# cubesatsim-main-1_0.net
KiCad netlist of a schematic drawn in EAGLE
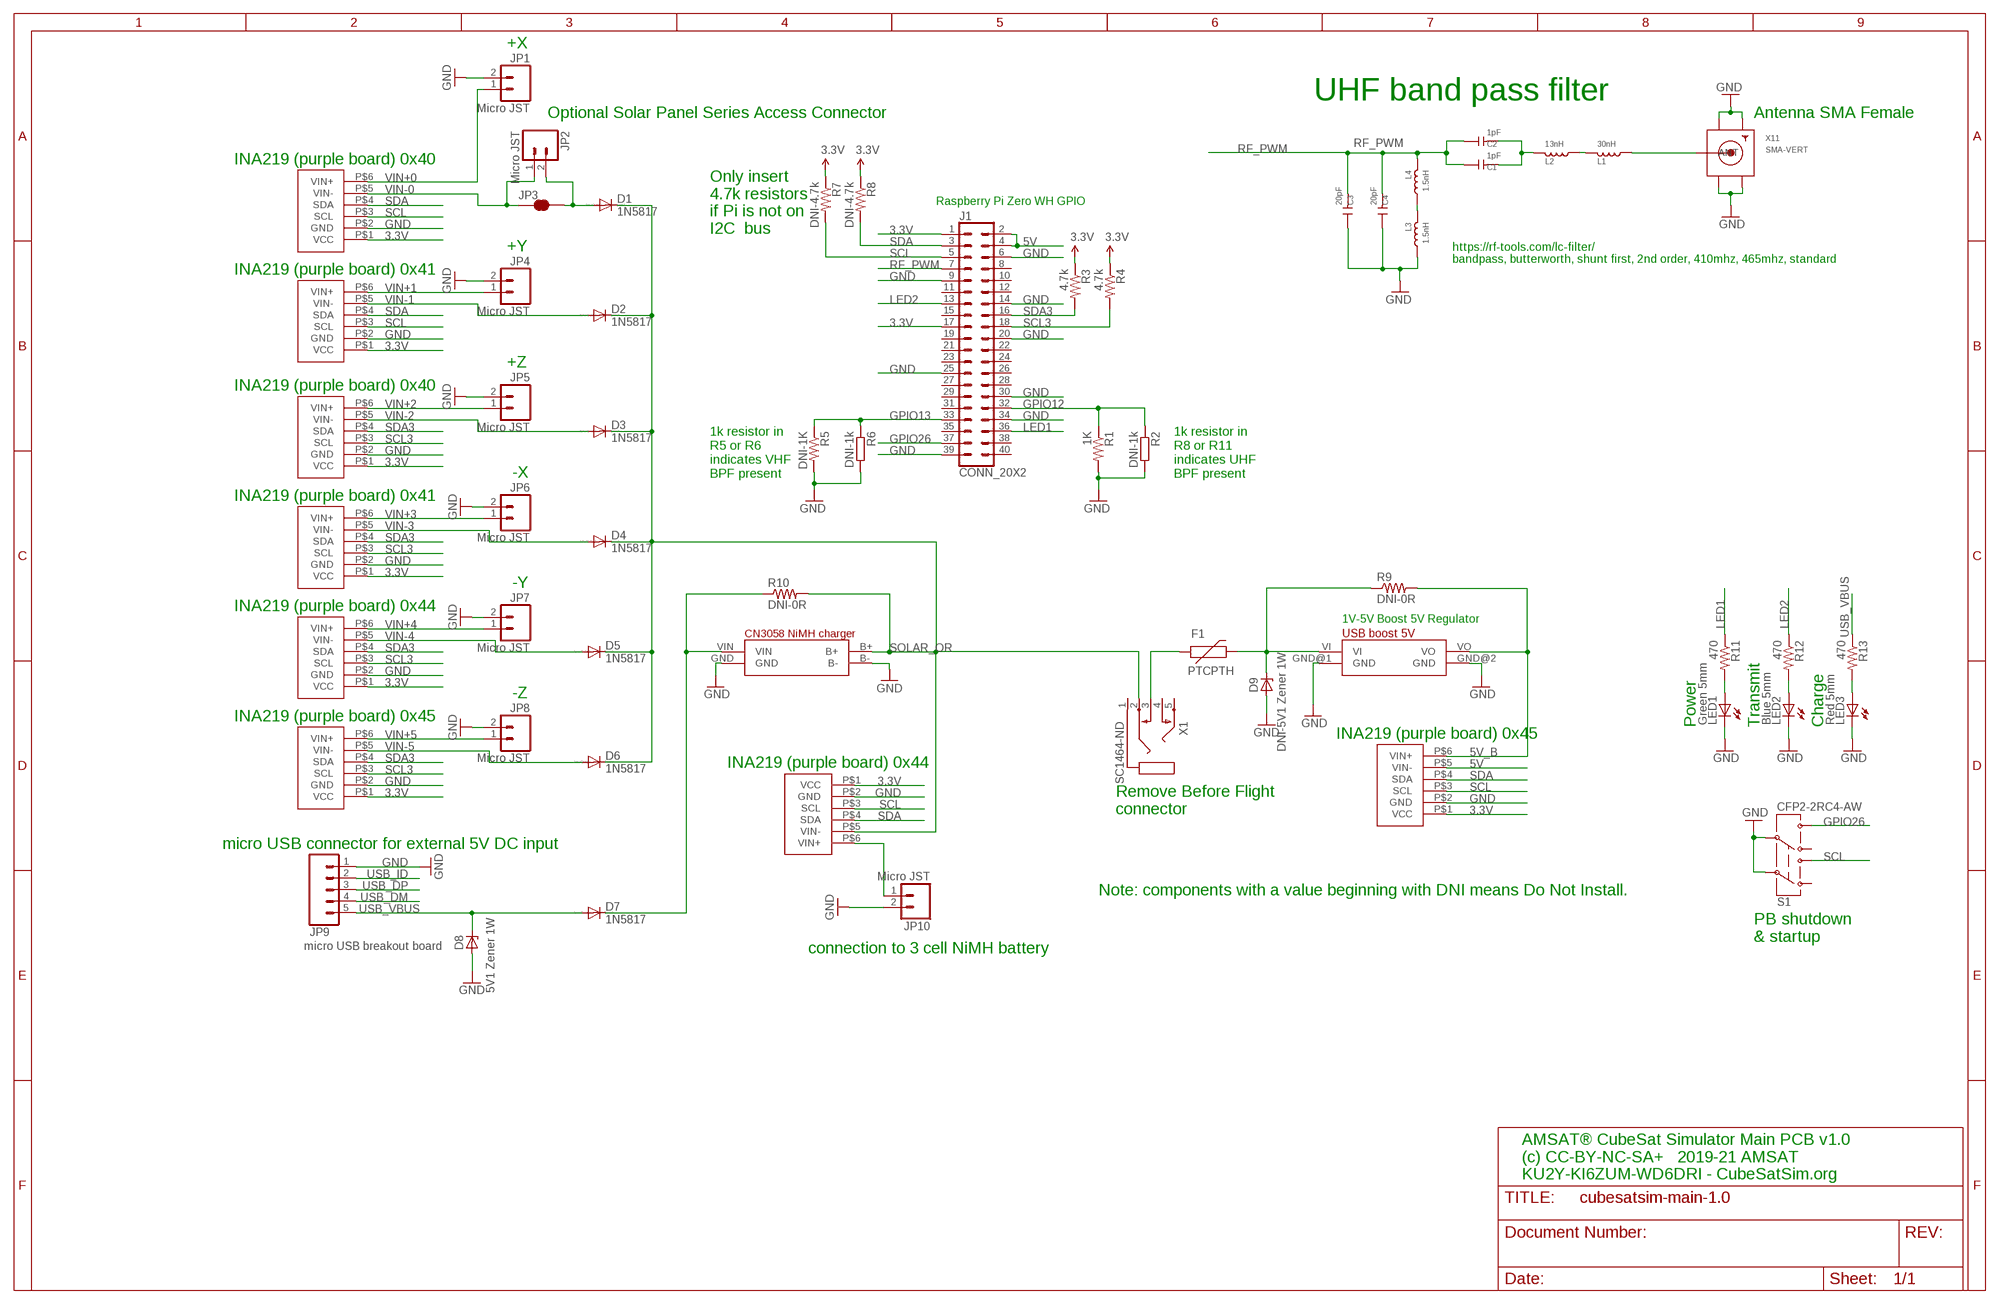
[diagram p0: schematic, sheet 1]

(export (version "E")
  (design (tool "Eeschema 10.0.6"))
  (components
    (comp (ref "C1")
      (value "1pF")
      (footprint "eagle-import:C0603")
      (libsource (lib "eagle-import") (part "CERAMIC-10PF-50V-5%-NPO(0603)"))
    )
    (comp (ref "C2")
      (value "1pF")
      (footprint "eagle-import:C0603")
      (libsource (lib "eagle-import") (part "CERAMIC-10PF-50V-5%-NPO(0603)"))
    )
    (comp (ref "C3")
      (value "20pF")
      (footprint "eagle-import:C0603")
      (libsource (lib "eagle-import") (part "CERAMIC-10PF-50V-5%-NPO(0603)"))
    )
    (comp (ref "C4")
      (value "20pF")
      (footprint "eagle-import:C0603")
      (libsource (lib "eagle-import") (part "CERAMIC-10PF-50V-5%-NPO(0603)"))
    )
    (comp (ref "D1")
      (value "1N5817")
      (footprint "eagle-import:D-2.5")
      (libsource (lib "eagle-import") (part "DIODE-D-2.5"))
    )
    (comp (ref "D2")
      (value "1N5817")
      (footprint "eagle-import:D-2.5")
      (libsource (lib "eagle-import") (part "DIODE-D-2.5"))
    )
    (comp (ref "D3")
      (value "1N5817")
      (footprint "eagle-import:D-2.5")
      (libsource (lib "eagle-import") (part "DIODE-D-2.5"))
    )
    (comp (ref "D4")
      (value "1N5817")
      (footprint "eagle-import:D-2.5")
      (libsource (lib "eagle-import") (part "DIODE-D-2.5"))
    )
    (comp (ref "D5")
      (value "1N5817")
      (footprint "eagle-import:D-2.5")
      (libsource (lib "eagle-import") (part "DIODE-D-2.5"))
    )
    (comp (ref "D6")
      (value "1N5817")
      (footprint "eagle-import:D-2.5")
      (libsource (lib "eagle-import") (part "DIODE-D-2.5"))
    )
    (comp (ref "D7")
      (value "1N5817")
      (footprint "eagle-import:D-2.5")
      (libsource (lib "eagle-import") (part "DIODE-D-2.5"))
    )
    (comp (ref "D8")
      (value "5V1 Zener 1W")
      (footprint "eagle-import:ZDIO-2.5")
      (libsource (lib "eagle-import") (part "ZENER-DIODEZD-2.5"))
    )
    (comp (ref "D9")
      (value "DNI-5V1 Zener 1W")
      (footprint "eagle-import:ZDIO-2.5")
      (libsource (lib "eagle-import") (part "ZENER-DIODEZD-2.5"))
    )
    (comp (ref "F1")
      (value "PTCPTH")
      (footprint "eagle-import:PTC")
      (libsource (lib "eagle-import") (part "PTCPTH"))
    )
    (comp (ref "J1")
      (value "CONN_20X2")
      (footprint "eagle-import:2X20")
      (libsource (lib "eagle-import") (part "CONN_20X2"))
    )
    (comp (ref "JP1")
      (value "Micro JST")
      (footprint "eagle-import:JST-2-PTH-VERT")
      (libsource (lib "eagle-import") (part "M02JST-PTH-VERT"))
    )
    (comp (ref "JP2")
      (value "Micro JST")
      (footprint "eagle-import:JST-2-PTH-VERT")
      (libsource (lib "eagle-import") (part "M02JST-PTH-VERT"))
    )
    (comp (ref "JP3")
      (value "VDD-EN")
      (footprint "eagle-import:SMT-JUMPER_2_NC_TRACE_SILK")
      (libsource (lib "eagle-import") (part "JUMPER-SMT_2_NC_TRACE_SILK"))
    )
    (comp (ref "JP4")
      (value "Micro JST")
      (footprint "eagle-import:JST-2-PTH-VERT")
      (libsource (lib "eagle-import") (part "M02JST-PTH-VERT"))
    )
    (comp (ref "JP5")
      (value "Micro JST")
      (footprint "eagle-import:JST-2-PTH-VERT")
      (libsource (lib "eagle-import") (part "M02JST-PTH-VERT"))
    )
    (comp (ref "JP6")
      (value "Micro JST")
      (footprint "eagle-import:JST-2-PTH-VERT")
      (libsource (lib "eagle-import") (part "M02JST-PTH-VERT"))
    )
    (comp (ref "JP7")
      (value "Micro JST")
      (footprint "eagle-import:JST-2-PTH-VERT")
      (libsource (lib "eagle-import") (part "M02JST-PTH-VERT"))
    )
    (comp (ref "JP8")
      (value "Micro JST")
      (footprint "eagle-import:JST-2-PTH-VERT")
      (libsource (lib "eagle-import") (part "M02JST-PTH-VERT"))
    )
    (comp (ref "JP9")
      (value "micro USB breakout board")
      (footprint "eagle-import:1X05_NO_SILK")
      (libsource (lib "eagle-import") (part "M05NO_SILK"))
    )
    (comp (ref "JP10")
      (value "Micro JST")
      (footprint "eagle-import:JST-2-PTH-VERT")
      (libsource (lib "eagle-import") (part "M02JST-PTH-VERT"))
    )
    (comp (ref "L1")
      (value "30nH")
      (footprint "eagle-import:L0603")
      (fields (field (name "MPN") "BLM18AG121SN1D"))
      (libsource (lib "eagle-import") (part "SMD-FERRITE-CHIP-120-OHM-500MA(0603)"))
    )
    (comp (ref "L2")
      (value "13nH")
      (footprint "eagle-import:L0603")
      (fields (field (name "MPN") "BLM18AG121SN1D"))
      (libsource (lib "eagle-import") (part "SMD-FERRITE-CHIP-120-OHM-500MA(0603)"))
    )
    (comp (ref "L3")
      (value "1.5nH")
      (footprint "eagle-import:L0603")
      (fields (field (name "MPN") "BLM18AG121SN1D"))
      (libsource (lib "eagle-import") (part "SMD-FERRITE-CHIP-120-OHM-500MA(0603)"))
    )
    (comp (ref "L4")
      (value "1.5nH")
      (footprint "eagle-import:L0603")
      (fields (field (name "MPN") "BLM18AG121SN1D"))
      (libsource (lib "eagle-import") (part "SMD-FERRITE-CHIP-120-OHM-500MA(0603)"))
    )
    (comp (ref "LED1")
      (value "Green 5mm")
      (footprint "eagle-import:LED3MM")
      (libsource (lib "eagle-import") (part "LED3MM"))
    )
    (comp (ref "LED2")
      (value "Blue 5mm")
      (footprint "eagle-import:LED3MM")
      (libsource (lib "eagle-import") (part "LED3MM"))
    )
    (comp (ref "LED3")
      (value "Red 5mm")
      (footprint "eagle-import:LED3MM")
      (libsource (lib "eagle-import") (part "LED3MM"))
    )
    (comp (ref "R1")
      (value "1K")
      (footprint "eagle-import:AXIAL-0.1EZ")
      (libsource (lib "eagle-import") (part "RESISTORPTH-1/4W-VERT-KIT"))
    )
    (comp (ref "R2")
      (value "DNI-1k")
      (footprint "eagle-import:R0603")
      (libsource (lib "eagle-import") (part "R-EU_R0603"))
    )
    (comp (ref "R3")
      (value "4.7k")
      (footprint "eagle-import:AXIAL-0.1EZ")
      (libsource (lib "eagle-import") (part "RESISTORPTH-1/4W-VERT-KIT"))
    )
    (comp (ref "R4")
      (value "4.7k")
      (footprint "eagle-import:AXIAL-0.1EZ")
      (libsource (lib "eagle-import") (part "RESISTORPTH-1/4W-VERT-KIT"))
    )
    (comp (ref "R5")
      (value "DNI-1K")
      (footprint "eagle-import:AXIAL-0.1EZ")
      (libsource (lib "eagle-import") (part "RESISTORPTH-1/4W-VERT-KIT"))
    )
    (comp (ref "R6")
      (value "DNI-1k")
      (footprint "eagle-import:R0603")
      (libsource (lib "eagle-import") (part "R-EU_R0603"))
    )
    (comp (ref "R7")
      (value "DNI-4.7k")
      (footprint "eagle-import:AXIAL-0.1EZ")
      (libsource (lib "eagle-import") (part "RESISTORPTH-1/4W-VERT-KIT"))
    )
    (comp (ref "R8")
      (value "DNI-4.7k")
      (footprint "eagle-import:AXIAL-0.1EZ")
      (libsource (lib "eagle-import") (part "RESISTORPTH-1/4W-VERT-KIT"))
    )
    (comp (ref "R9")
      (value "DNI-0R")
      (footprint "eagle-import:AXIAL-0.1EZ")
      (libsource (lib "eagle-import") (part "RESISTORPTH-1/4W-VERT-KIT"))
    )
    (comp (ref "R10")
      (value "DNI-0R")
      (footprint "eagle-import:AXIAL-0.1EZ")
      (libsource (lib "eagle-import") (part "RESISTORPTH-1/4W-VERT-KIT"))
    )
    (comp (ref "R11")
      (value "470")
      (footprint "eagle-import:AXIAL-0.1EZ")
      (libsource (lib "eagle-import") (part "RESISTORPTH-1/4W-VERT-KIT"))
    )
    (comp (ref "R12")
      (value "470")
      (footprint "eagle-import:AXIAL-0.1EZ")
      (libsource (lib "eagle-import") (part "RESISTORPTH-1/4W-VERT-KIT"))
    )
    (comp (ref "R13")
      (value "470")
      (footprint "eagle-import:AXIAL-0.1EZ")
      (libsource (lib "eagle-import") (part "RESISTORPTH-1/4W-VERT-KIT"))
    )
    (comp (ref "S1")
      (value "CFP2-2RC4-AW")
      (footprint "eagle-import:OS")
      (libsource (lib "eagle-import") (part "SWITCH-DPDTOS"))
    )
    (comp (ref "U1")
      (value "INA219 purple board")
      (footprint "eagle-import:INA219")
      (libsource (lib "eagle-import") (part "INA219"))
    )
    (comp (ref "U2")
      (value "INA219 purple board")
      (footprint "eagle-import:INA219")
      (libsource (lib "eagle-import") (part "INA219"))
    )
    (comp (ref "U3")
      (value "INA219 purple board")
      (footprint "eagle-import:INA219")
      (libsource (lib "eagle-import") (part "INA219"))
    )
    (comp (ref "U4")
      (value "INA219 purple board")
      (footprint "eagle-import:INA219")
      (libsource (lib "eagle-import") (part "INA219"))
    )
    (comp (ref "U5")
      (value "INA219 purple board")
      (footprint "eagle-import:INA219")
      (libsource (lib "eagle-import") (part "INA219"))
    )
    (comp (ref "U6")
      (value "CN3085-MODULE")
      (footprint "eagle-import:CN3085-MODULE")
      (libsource (lib "eagle-import") (part "CN3085-MODULE"))
    )
    (comp (ref "U7")
      (value "1V-5V Boost 5V Regulator")
      (footprint "eagle-import:USB-BOOST")
      (libsource (lib "eagle-import") (part "USB-BOOST"))
    )
    (comp (ref "U8")
      (value "INA219 purple board")
      (footprint "eagle-import:INA219")
      (libsource (lib "eagle-import") (part "INA219"))
    )
    (comp (ref "U9")
      (value "INA219 purple board")
      (footprint "eagle-import:INA219")
      (libsource (lib "eagle-import") (part "INA219"))
    )
    (comp (ref "U10")
      (value "INA219 purple board")
      (footprint "eagle-import:INA219")
      (libsource (lib "eagle-import") (part "INA219"))
    )
    (comp (ref "X1")
      (value "SC1464-ND")
      (footprint "eagle-import:PG203J")
      (libsource (lib "eagle-import") (part "PG203J"))
    )
    (comp (ref "X11")
      (value "SMA-VERT")
      (footprint "eagle-import:SMA-VERT")
      (libsource (lib "eagle-import") (part "SMA-VERT"))
    )
  )
  (nets
    (net (code "1") (name "/5V") (class "Default")
      (node (ref "J1") (pin "2") (pinfunction "2_2") (pintype "passive"))
      (node (ref "J1") (pin "4") (pinfunction "4_4") (pintype "passive"))
      (node (ref "U9") (pin "P$5") (pinfunction "VIN-_P$5") (pintype "bidirectional"))
    )
    (net (code "2") (name "/5V_B") (class "Default")
      (node (ref "R9") (pin "P$2") (pinfunction "2_P$2") (pintype "passive"))
      (node (ref "U7") (pin "VO") (pinfunction "VO_VO") (pintype "bidirectional"))
      (node (ref "U9") (pin "P$6") (pinfunction "VIN+_P$6") (pintype "bidirectional"))
    )
    (net (code "3") (name "/GPIO12") (class "Default")
      (node (ref "J1") (pin "32") (pinfunction "32_32") (pintype "passive"))
      (node (ref "R1") (pin "P$1") (pinfunction "1_P$1") (pintype "passive"))
      (node (ref "R2") (pin "1") (pinfunction "1_1") (pintype "passive"))
    )
    (net (code "4") (name "/GPIO13") (class "Default")
      (node (ref "J1") (pin "33") (pinfunction "33_33") (pintype "passive"))
      (node (ref "R5") (pin "P$1") (pinfunction "1_P$1") (pintype "passive"))
      (node (ref "R6") (pin "1") (pinfunction "1_1") (pintype "passive"))
    )
    (net (code "5") (name "/GPIO26") (class "Default")
      (node (ref "J1") (pin "37") (pinfunction "37_37") (pintype "passive"))
      (node (ref "S1") (pin "6") (pinfunction "6_6") (pintype "bidirectional"))
    )
    (net (code "6") (name "/LED1") (class "Default")
      (node (ref "J1") (pin "36") (pinfunction "36_36") (pintype "passive"))
      (node (ref "R11") (pin "P$1") (pinfunction "1_P$1") (pintype "passive"))
    )
    (net (code "7") (name "/LED2") (class "Default")
      (node (ref "J1") (pin "13") (pinfunction "13_13") (pintype "passive"))
      (node (ref "R12") (pin "P$1") (pinfunction "1_P$1") (pintype "passive"))
    )
    (net (code "8") (name "/RF_PWM") (class "Default")
      (node (ref "C1") (pin "1") (pinfunction "1_1") (pintype "passive"))
      (node (ref "C2") (pin "1") (pinfunction "1_1") (pintype "passive"))
      (node (ref "C3") (pin "2") (pinfunction "2_2") (pintype "passive"))
      (node (ref "C4") (pin "2") (pinfunction "2_2") (pintype "passive"))
      (node (ref "J1") (pin "7") (pinfunction "7_7") (pintype "passive"))
      (node (ref "L4") (pin "1") (pinfunction "1_1") (pintype "passive"))
    )
    (net (code "9") (name "/SCL") (class "Default")
      (node (ref "J1") (pin "5") (pinfunction "5_5") (pintype "passive"))
      (node (ref "R7") (pin "P$2") (pinfunction "2_P$2") (pintype "passive"))
      (node (ref "S1") (pin "3") (pinfunction "3_3") (pintype "bidirectional"))
      (node (ref "U1") (pin "P$3") (pinfunction "SCL_P$3") (pintype "bidirectional"))
      (node (ref "U10") (pin "P$3") (pinfunction "SCL_P$3") (pintype "bidirectional"))
      (node (ref "U2") (pin "P$3") (pinfunction "SCL_P$3") (pintype "bidirectional"))
      (node (ref "U9") (pin "P$3") (pinfunction "SCL_P$3") (pintype "bidirectional"))
    )
    (net (code "10") (name "/SCL3") (class "Default")
      (node (ref "J1") (pin "18") (pinfunction "18_18") (pintype "passive"))
      (node (ref "R4") (pin "P$2") (pinfunction "2_P$2") (pintype "passive"))
      (node (ref "U3") (pin "P$3") (pinfunction "SCL_P$3") (pintype "bidirectional"))
      (node (ref "U4") (pin "P$3") (pinfunction "SCL_P$3") (pintype "bidirectional"))
      (node (ref "U5") (pin "P$3") (pinfunction "SCL_P$3") (pintype "bidirectional"))
      (node (ref "U8") (pin "P$3") (pinfunction "SCL_P$3") (pintype "bidirectional"))
    )
    (net (code "11") (name "/SDA") (class "Default")
      (node (ref "J1") (pin "3") (pinfunction "3_3") (pintype "passive"))
      (node (ref "R8") (pin "P$2") (pinfunction "2_P$2") (pintype "passive"))
      (node (ref "U1") (pin "P$4") (pinfunction "SDA_P$4") (pintype "bidirectional"))
      (node (ref "U10") (pin "P$4") (pinfunction "SDA_P$4") (pintype "bidirectional"))
      (node (ref "U2") (pin "P$4") (pinfunction "SDA_P$4") (pintype "bidirectional"))
      (node (ref "U9") (pin "P$4") (pinfunction "SDA_P$4") (pintype "bidirectional"))
    )
    (net (code "12") (name "/SDA3") (class "Default")
      (node (ref "J1") (pin "16") (pinfunction "16_16") (pintype "passive"))
      (node (ref "R3") (pin "P$2") (pinfunction "2_P$2") (pintype "passive"))
      (node (ref "U3") (pin "P$4") (pinfunction "SDA_P$4") (pintype "bidirectional"))
      (node (ref "U4") (pin "P$4") (pinfunction "SDA_P$4") (pintype "bidirectional"))
      (node (ref "U5") (pin "P$4") (pinfunction "SDA_P$4") (pintype "bidirectional"))
      (node (ref "U8") (pin "P$4") (pinfunction "SDA_P$4") (pintype "bidirectional"))
    )
    (net (code "13") (name "/SOLAR_OR") (class "Default")
      (node (ref "D1") (pin "C") (pinfunction "C_C") (pintype "passive"))
      (node (ref "D2") (pin "C") (pinfunction "C_C") (pintype "passive"))
      (node (ref "D3") (pin "C") (pinfunction "C_C") (pintype "passive"))
      (node (ref "D4") (pin "C") (pinfunction "C_C") (pintype "passive"))
      (node (ref "D5") (pin "C") (pinfunction "C_C") (pintype "passive"))
      (node (ref "D6") (pin "C") (pinfunction "C_C") (pintype "passive"))
      (node (ref "R10") (pin "P$2") (pinfunction "2_P$2") (pintype "passive"))
      (node (ref "U10") (pin "P$5") (pinfunction "VIN-_P$5") (pintype "bidirectional"))
      (node (ref "U6") (pin "B+") (pinfunction "B+_B+") (pintype "bidirectional"))
      (node (ref "X1") (pin "2") (pinfunction "2_2") (pintype "passive"))
    )
    (net (code "14") (name "/USB_DM") (class "Default")
      (node (ref "JP9") (pin "4") (pinfunction "4_4") (pintype "passive"))
    )
    (net (code "15") (name "/USB_DP") (class "Default")
      (node (ref "JP9") (pin "3") (pinfunction "3_3") (pintype "passive"))
    )
    (net (code "16") (name "/USB_ID") (class "Default")
      (node (ref "JP9") (pin "2") (pinfunction "2_2") (pintype "passive"))
    )
    (net (code "17") (name "/USB_VBUS") (class "Default")
      (node (ref "D7") (pin "A") (pinfunction "A_A") (pintype "passive"))
      (node (ref "D8") (pin "C") (pinfunction "C_C") (pintype "passive"))
      (node (ref "JP9") (pin "5") (pinfunction "5_5") (pintype "passive"))
      (node (ref "R13") (pin "P$1") (pinfunction "1_P$1") (pintype "passive"))
    )
    (net (code "18") (name "/VIN+0") (class "Default")
      (node (ref "JP1") (pin "1") (pinfunction "1_1") (pintype "passive"))
      (node (ref "U1") (pin "P$6") (pinfunction "VIN+_P$6") (pintype "bidirectional"))
    )
    (net (code "19") (name "/VIN+1") (class "Default")
      (node (ref "JP4") (pin "1") (pinfunction "1_1") (pintype "passive"))
      (node (ref "U2") (pin "P$6") (pinfunction "VIN+_P$6") (pintype "bidirectional"))
    )
    (net (code "20") (name "/VIN+2") (class "Default")
      (node (ref "JP5") (pin "1") (pinfunction "1_1") (pintype "passive"))
      (node (ref "U3") (pin "P$6") (pinfunction "VIN+_P$6") (pintype "bidirectional"))
    )
    (net (code "21") (name "/VIN+3") (class "Default")
      (node (ref "JP6") (pin "1") (pinfunction "1_1") (pintype "passive"))
      (node (ref "U4") (pin "P$6") (pinfunction "VIN+_P$6") (pintype "bidirectional"))
    )
    (net (code "22") (name "/VIN+4") (class "Default")
      (node (ref "JP7") (pin "1") (pinfunction "1_1") (pintype "passive"))
      (node (ref "U5") (pin "P$6") (pinfunction "VIN+_P$6") (pintype "bidirectional"))
    )
    (net (code "23") (name "/VIN+5") (class "Default")
      (node (ref "JP8") (pin "1") (pinfunction "1_1") (pintype "passive"))
      (node (ref "U8") (pin "P$6") (pinfunction "VIN+_P$6") (pintype "bidirectional"))
    )
    (net (code "24") (name "/VIN-0") (class "Default")
      (node (ref "JP2") (pin "1") (pinfunction "1_1") (pintype "passive"))
      (node (ref "JP3") (pin "1") (pinfunction "1_1") (pintype "passive"))
      (node (ref "U1") (pin "P$5") (pinfunction "VIN-_P$5") (pintype "bidirectional"))
    )
    (net (code "25") (name "/VIN-1") (class "Default")
      (node (ref "D2") (pin "A") (pinfunction "A_A") (pintype "passive"))
      (node (ref "U2") (pin "P$5") (pinfunction "VIN-_P$5") (pintype "bidirectional"))
    )
    (net (code "26") (name "/VIN-2") (class "Default")
      (node (ref "D3") (pin "A") (pinfunction "A_A") (pintype "passive"))
      (node (ref "U3") (pin "P$5") (pinfunction "VIN-_P$5") (pintype "bidirectional"))
    )
    (net (code "27") (name "/VIN-3") (class "Default")
      (node (ref "D4") (pin "A") (pinfunction "A_A") (pintype "passive"))
      (node (ref "U4") (pin "P$5") (pinfunction "VIN-_P$5") (pintype "bidirectional"))
    )
    (net (code "28") (name "/VIN-4") (class "Default")
      (node (ref "D5") (pin "A") (pinfunction "A_A") (pintype "passive"))
      (node (ref "U5") (pin "P$5") (pinfunction "VIN-_P$5") (pintype "bidirectional"))
    )
    (net (code "29") (name "/VIN-5") (class "Default")
      (node (ref "D6") (pin "A") (pinfunction "A_A") (pintype "passive"))
      (node (ref "U8") (pin "P$5") (pinfunction "VIN-_P$5") (pintype "bidirectional"))
    )
    (net (code "30") (name "3.3V") (class "Default")
      (node (ref "J1") (pin "1") (pinfunction "1_1") (pintype "passive"))
      (node (ref "J1") (pin "17") (pinfunction "17_17") (pintype "passive"))
      (node (ref "R3") (pin "P$1") (pinfunction "1_P$1") (pintype "passive"))
      (node (ref "R4") (pin "P$1") (pinfunction "1_P$1") (pintype "passive"))
      (node (ref "R7") (pin "P$1") (pinfunction "1_P$1") (pintype "passive"))
      (node (ref "R8") (pin "P$1") (pinfunction "1_P$1") (pintype "passive"))
      (node (ref "U1") (pin "P$1") (pinfunction "VCC_P$1") (pintype "bidirectional"))
      (node (ref "U10") (pin "P$1") (pinfunction "VCC_P$1") (pintype "bidirectional"))
      (node (ref "U2") (pin "P$1") (pinfunction "VCC_P$1") (pintype "bidirectional"))
      (node (ref "U3") (pin "P$1") (pinfunction "VCC_P$1") (pintype "bidirectional"))
      (node (ref "U4") (pin "P$1") (pinfunction "VCC_P$1") (pintype "bidirectional"))
      (node (ref "U5") (pin "P$1") (pinfunction "VCC_P$1") (pintype "bidirectional"))
      (node (ref "U8") (pin "P$1") (pinfunction "VCC_P$1") (pintype "bidirectional"))
      (node (ref "U9") (pin "P$1") (pinfunction "VCC_P$1") (pintype "bidirectional"))
    )
    (net (code "31") (name "GND") (class "Default")
      (node (ref "C3") (pin "1") (pinfunction "1_1") (pintype "passive"))
      (node (ref "C4") (pin "1") (pinfunction "1_1") (pintype "passive"))
      (node (ref "D8") (pin "A") (pinfunction "A_A") (pintype "passive"))
      (node (ref "D9") (pin "A") (pinfunction "A_A") (pintype "passive"))
      (node (ref "J1") (pin "14") (pinfunction "14_14") (pintype "passive"))
      (node (ref "J1") (pin "20") (pinfunction "20_20") (pintype "passive"))
      (node (ref "J1") (pin "25") (pinfunction "25_25") (pintype "passive"))
      (node (ref "J1") (pin "30") (pinfunction "30_30") (pintype "passive"))
      (node (ref "J1") (pin "34") (pinfunction "34_34") (pintype "passive"))
      (node (ref "J1") (pin "39") (pinfunction "39_39") (pintype "passive"))
      (node (ref "J1") (pin "6") (pinfunction "6_6") (pintype "passive"))
      (node (ref "J1") (pin "9") (pinfunction "9_9") (pintype "passive"))
      (node (ref "JP1") (pin "2") (pinfunction "2_2") (pintype "passive"))
      (node (ref "JP10") (pin "2") (pinfunction "2_2") (pintype "passive"))
      (node (ref "JP4") (pin "2") (pinfunction "2_2") (pintype "passive"))
      (node (ref "JP5") (pin "2") (pinfunction "2_2") (pintype "passive"))
      (node (ref "JP6") (pin "2") (pinfunction "2_2") (pintype "passive"))
      (node (ref "JP7") (pin "2") (pinfunction "2_2") (pintype "passive"))
      (node (ref "JP8") (pin "2") (pinfunction "2_2") (pintype "passive"))
      (node (ref "JP9") (pin "1") (pinfunction "1_1") (pintype "passive"))
      (node (ref "L3") (pin "2") (pinfunction "2_2") (pintype "passive"))
      (node (ref "LED1") (pin "K") (pinfunction "C_K") (pintype "passive"))
      (node (ref "LED2") (pin "K") (pinfunction "C_K") (pintype "passive"))
      (node (ref "LED3") (pin "K") (pinfunction "C_K") (pintype "passive"))
      (node (ref "R1") (pin "P$2") (pinfunction "2_P$2") (pintype "passive"))
      (node (ref "R2") (pin "2") (pinfunction "2_2") (pintype "passive"))
      (node (ref "R5") (pin "P$2") (pinfunction "2_P$2") (pintype "passive"))
      (node (ref "R6") (pin "2") (pinfunction "2_2") (pintype "passive"))
      (node (ref "S1") (pin "2") (pinfunction "2_2") (pintype "bidirectional"))
      (node (ref "S1") (pin "5") (pinfunction "5_5") (pintype "bidirectional"))
      (node (ref "U1") (pin "P$2") (pinfunction "GND_P$2") (pintype "bidirectional"))
      (node (ref "U10") (pin "P$2") (pinfunction "GND_P$2") (pintype "bidirectional"))
      (node (ref "U2") (pin "P$2") (pinfunction "GND_P$2") (pintype "bidirectional"))
      (node (ref "U3") (pin "P$2") (pinfunction "GND_P$2") (pintype "bidirectional"))
      (node (ref "U4") (pin "P$2") (pinfunction "GND_P$2") (pintype "bidirectional"))
      (node (ref "U5") (pin "P$2") (pinfunction "GND_P$2") (pintype "bidirectional"))
      (node (ref "U6") (pin "B-") (pinfunction "B-_B-") (pintype "bidirectional"))
      (node (ref "U6") (pin "GND") (pinfunction "GND_GND") (pintype "bidirectional"))
      (node (ref "U7") (pin "GND@1") (pinfunction "GND_GND@1") (pintype "bidirectional"))
      (node (ref "U7") (pin "GND@2") (pinfunction "GND_GND@2") (pintype "bidirectional"))
      (node (ref "U8") (pin "P$2") (pinfunction "GND_P$2") (pintype "bidirectional"))
      (node (ref "U9") (pin "P$2") (pinfunction "GND_P$2") (pintype "bidirectional"))
      (node (ref "X11") (pin "GND1") (pinfunction "GND1_GND1") (pintype "power_in"))
      (node (ref "X11") (pin "GND2") (pinfunction "GND2_GND2") (pintype "power_in"))
      (node (ref "X11") (pin "GND3") (pinfunction "GND3_GND3") (pintype "power_in"))
      (node (ref "X11") (pin "GND4") (pinfunction "GND4_GND4") (pintype "power_in"))
    )
    (net (code "32") (name "Net-(C1-Pad2)") (class "Default")
      (node (ref "C1") (pin "2") (pinfunction "2_2") (pintype "passive"))
      (node (ref "C2") (pin "2") (pinfunction "2_2") (pintype "passive"))
      (node (ref "L2") (pin "1") (pinfunction "1_1") (pintype "passive"))
    )
    (net (code "33") (name "Net-(D1-PadA)") (class "Default")
      (node (ref "D1") (pin "A") (pinfunction "A_A") (pintype "passive"))
      (node (ref "JP2") (pin "2") (pinfunction "2_2") (pintype "passive"))
      (node (ref "JP3") (pin "2") (pinfunction "2_2") (pintype "passive"))
    )
    (net (code "34") (name "Net-(F1-1)") (class "Default")
      (node (ref "F1") (pin "P$1") (pinfunction "1_P$1") (pintype "bidirectional"))
      (node (ref "X1") (pin "3") (pinfunction "3_3") (pintype "passive"))
    )
    (net (code "35") (name "Net-(F1-2)") (class "Default")
      (node (ref "D9") (pin "C") (pinfunction "C_C") (pintype "passive"))
      (node (ref "F1") (pin "P$2") (pinfunction "2_P$2") (pintype "bidirectional"))
      (node (ref "R9") (pin "P$1") (pinfunction "1_P$1") (pintype "passive"))
      (node (ref "U7") (pin "VI") (pinfunction "VI_VI") (pintype "bidirectional"))
    )
    (net (code "36") (name "Net-(L1-Pad1)") (class "Default")
      (node (ref "L1") (pin "1") (pinfunction "1_1") (pintype "passive"))
      (node (ref "L2") (pin "2") (pinfunction "2_2") (pintype "passive"))
    )
    (net (code "37") (name "Net-(L3-Pad1)") (class "Default")
      (node (ref "L3") (pin "1") (pinfunction "1_1") (pintype "passive"))
      (node (ref "L4") (pin "2") (pinfunction "2_2") (pintype "passive"))
    )
    (net (code "38") (name "Net-(R10-1)") (class "Default")
      (node (ref "D7") (pin "C") (pinfunction "C_C") (pintype "passive"))
      (node (ref "R10") (pin "P$1") (pinfunction "1_P$1") (pintype "passive"))
      (node (ref "U6") (pin "VIN") (pinfunction "VIN_VIN") (pintype "bidirectional"))
    )
    (net (code "39") (name "Net-(R11-2)") (class "Default")
      (node (ref "LED1") (pin "A") (pinfunction "A_A") (pintype "passive"))
      (node (ref "R11") (pin "P$2") (pinfunction "2_P$2") (pintype "passive"))
    )
    (net (code "40") (name "Net-(R12-2)") (class "Default")
      (node (ref "LED2") (pin "A") (pinfunction "A_A") (pintype "passive"))
      (node (ref "R12") (pin "P$2") (pinfunction "2_P$2") (pintype "passive"))
    )
    (net (code "41") (name "Net-(R13-2)") (class "Default")
      (node (ref "LED3") (pin "A") (pinfunction "A_A") (pintype "passive"))
      (node (ref "R13") (pin "P$2") (pinfunction "2_P$2") (pintype "passive"))
    )
    (net (code "42") (name "Net-(U10-VIN+)") (class "Default")
      (node (ref "JP10") (pin "1") (pinfunction "1_1") (pintype "passive"))
      (node (ref "U10") (pin "P$6") (pinfunction "VIN+_P$6") (pintype "bidirectional"))
    )
    (net (code "43") (name "Net-(X11-ANT)") (class "Default")
      (node (ref "L1") (pin "2") (pinfunction "2_2") (pintype "passive"))
      (node (ref "X11") (pin "ANTENNA") (pinfunction "ANT_ANTENNA") (pintype "bidirectional"))
    )
    (net (code "44") (name "unconnected-(J1-Pad8)") (class "Default")
      (node (ref "J1") (pin "8") (pinfunction "8_8") (pintype "passive"))
    )
    (net (code "45") (name "unconnected-(J1-Pad10)") (class "Default")
      (node (ref "J1") (pin "10") (pinfunction "10_10") (pintype "passive"))
    )
    (net (code "46") (name "unconnected-(J1-Pad11)") (class "Default")
      (node (ref "J1") (pin "11") (pinfunction "11_11") (pintype "passive"))
    )
    (net (code "47") (name "unconnected-(J1-Pad12)") (class "Default")
      (node (ref "J1") (pin "12") (pinfunction "12_12") (pintype "passive"))
    )
    (net (code "48") (name "unconnected-(J1-Pad15)") (class "Default")
      (node (ref "J1") (pin "15") (pinfunction "15_15") (pintype "passive"))
    )
    (net (code "49") (name "unconnected-(J1-Pad19)") (class "Default")
      (node (ref "J1") (pin "19") (pinfunction "19_19") (pintype "passive"))
    )
    (net (code "50") (name "unconnected-(J1-Pad21)") (class "Default")
      (node (ref "J1") (pin "21") (pinfunction "21_21") (pintype "passive"))
    )
    (net (code "51") (name "unconnected-(J1-Pad22)") (class "Default")
      (node (ref "J1") (pin "22") (pinfunction "22_22") (pintype "passive"))
    )
    (net (code "52") (name "unconnected-(J1-Pad23)") (class "Default")
      (node (ref "J1") (pin "23") (pinfunction "23_23") (pintype "passive"))
    )
    (net (code "53") (name "unconnected-(J1-Pad24)") (class "Default")
      (node (ref "J1") (pin "24") (pinfunction "24_24") (pintype "passive"))
    )
    (net (code "54") (name "unconnected-(J1-Pad26)") (class "Default")
      (node (ref "J1") (pin "26") (pinfunction "26_26") (pintype "passive"))
    )
    (net (code "55") (name "unconnected-(J1-Pad27)") (class "Default")
      (node (ref "J1") (pin "27") (pinfunction "27_27") (pintype "passive"))
    )
    (net (code "56") (name "unconnected-(J1-Pad28)") (class "Default")
      (node (ref "J1") (pin "28") (pinfunction "28_28") (pintype "passive"))
    )
    (net (code "57") (name "unconnected-(J1-Pad29)") (class "Default")
      (node (ref "J1") (pin "29") (pinfunction "29_29") (pintype "passive"))
    )
    (net (code "58") (name "unconnected-(J1-Pad31)") (class "Default")
      (node (ref "J1") (pin "31") (pinfunction "31_31") (pintype "passive"))
    )
    (net (code "59") (name "unconnected-(J1-Pad35)") (class "Default")
      (node (ref "J1") (pin "35") (pinfunction "35_35") (pintype "passive"))
    )
    (net (code "60") (name "unconnected-(J1-Pad38)") (class "Default")
      (node (ref "J1") (pin "38") (pinfunction "38_38") (pintype "passive"))
    )
    (net (code "61") (name "unconnected-(J1-Pad40)") (class "Default")
      (node (ref "J1") (pin "40") (pinfunction "40_40") (pintype "passive"))
    )
    (net (code "62") (name "unconnected-(S1-Pad1)") (class "Default")
      (node (ref "S1") (pin "1") (pinfunction "1_1") (pintype "bidirectional"))
    )
    (net (code "63") (name "unconnected-(S1-Pad4)") (class "Default")
      (node (ref "S1") (pin "4") (pinfunction "4_4") (pintype "bidirectional"))
    )
    (net (code "64") (name "unconnected-(X1-Pad1)") (class "Default")
      (node (ref "X1") (pin "1") (pinfunction "1_1") (pintype "passive"))
    )
    (net (code "65") (name "unconnected-(X1-Pad4)") (class "Default")
      (node (ref "X1") (pin "4") (pinfunction "4_4") (pintype "passive"))
    )
    (net (code "66") (name "unconnected-(X1-Pad5)") (class "Default")
      (node (ref "X1") (pin "5") (pinfunction "5_5") (pintype "passive"))
    )
  )
)
